# v7-flex2811_single.net
KiCad netlist of a schematic drawn in EAGLE
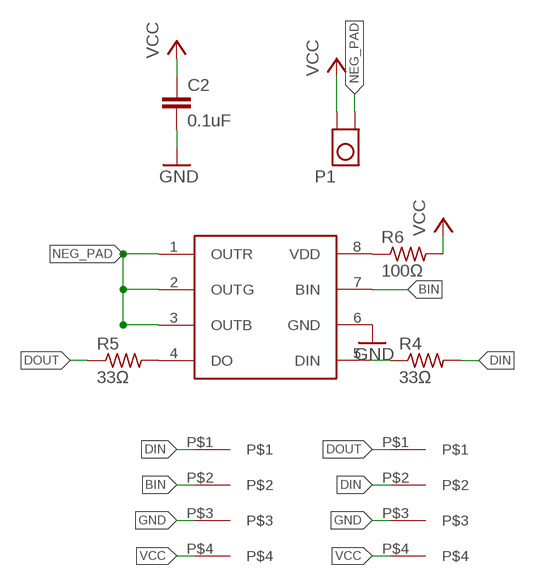
[diagram p0: schematic, sheet 1]

(export (version "E")
  (design (tool "Eeschema 10.0.6"))
  (components
    (comp (ref "C2")
      (value "0.1uF")
      (footprint "eagle-import:C0201")
      (libsource (lib "eagle-import") (part "C-EUC0201"))
    )
    (comp (ref "P1")
      (value "TP_4MM_MED_PAD")
      (footprint "eagle-import:TP_4MM_MED_PAD")
      (libsource (lib "eagle-import") (part "TP_4MM_MED_PAD"))
    )
    (comp (ref "R4")
      (value "33Ω")
      (footprint "eagle-import:R0201")
      (libsource (lib "eagle-import") (part "R-US_R0201"))
    )
    (comp (ref "R5")
      (value "33Ω")
      (footprint "eagle-import:R0201")
      (libsource (lib "eagle-import") (part "R-US_R0201"))
    )
    (comp (ref "R6")
      (value "100Ω")
      (footprint "eagle-import:R0201")
      (libsource (lib "eagle-import") (part "R-US_R0201"))
    )
    (comp (ref "U$3")
      (value "4PAD")
      (footprint "eagle-import:4PAD")
      (libsource (lib "eagle-import") (part "4PAD"))
    )
    (comp (ref "U$4")
      (value "4PAD")
      (footprint "eagle-import:4PAD")
      (libsource (lib "eagle-import") (part "4PAD"))
    )
    (comp (ref "U1")
      (value "WS2818")
      (footprint "eagle-import:SO08")
      (libsource (lib "eagle-import") (part "WS2818"))
    )
  )
  (nets
    (net (code "1") (name "BIN") (class "Default")
      (node (ref "U$3") (pin "P$2") (pinfunction "P$2_P$2") (pintype "bidirectional"))
      (node (ref "U1") (pin "7") (pinfunction "BIN_7") (pintype "bidirectional"))
    )
    (net (code "2") (name "DIN") (class "Default")
      (node (ref "R4") (pin "2") (pinfunction "2_2") (pintype "passive"))
      (node (ref "U$3") (pin "P$1") (pinfunction "P$1_P$1") (pintype "bidirectional"))
      (node (ref "U$4") (pin "P$2") (pinfunction "P$2_P$2") (pintype "bidirectional"))
    )
    (net (code "3") (name "DOUT") (class "Default")
      (node (ref "R5") (pin "1") (pinfunction "1_1") (pintype "passive"))
      (node (ref "U$4") (pin "P$1") (pinfunction "P$1_P$1") (pintype "bidirectional"))
    )
    (net (code "4") (name "GND") (class "Default")
      (node (ref "C2") (pin "2") (pinfunction "2_2") (pintype "passive"))
      (node (ref "U$3") (pin "P$3") (pinfunction "P$3_P$3") (pintype "bidirectional"))
      (node (ref "U$4") (pin "P$3") (pinfunction "P$3_P$3") (pintype "bidirectional"))
      (node (ref "U1") (pin "6") (pinfunction "GND_6") (pintype "bidirectional"))
    )
    (net (code "5") (name "NEG_PAD") (class "Default")
      (node (ref "P1") (pin "P$1") (pinfunction "0_P$1") (pintype "bidirectional"))
      (node (ref "U1") (pin "1") (pinfunction "OUTR_1") (pintype "bidirectional"))
      (node (ref "U1") (pin "2") (pinfunction "OUTG_2") (pintype "bidirectional"))
      (node (ref "U1") (pin "3") (pinfunction "OUTB_3") (pintype "bidirectional"))
    )
    (net (code "6") (name "Net-(U1-DIN)") (class "Default")
      (node (ref "R4") (pin "1") (pinfunction "1_1") (pintype "passive"))
      (node (ref "U1") (pin "5") (pinfunction "DIN_5") (pintype "bidirectional"))
    )
    (net (code "7") (name "Net-(U1-DO)") (class "Default")
      (node (ref "R5") (pin "2") (pinfunction "2_2") (pintype "passive"))
      (node (ref "U1") (pin "4") (pinfunction "DO_4") (pintype "bidirectional"))
    )
    (net (code "8") (name "Net-(U1-VDD)") (class "Default")
      (node (ref "R6") (pin "1") (pinfunction "1_1") (pintype "passive"))
      (node (ref "U1") (pin "8") (pinfunction "VDD_8") (pintype "bidirectional"))
    )
    (net (code "9") (name "VCC") (class "Default")
      (node (ref "C2") (pin "1") (pinfunction "1_1") (pintype "passive"))
      (node (ref "P1") (pin "P$2") (pinfunction "1_P$2") (pintype "bidirectional"))
      (node (ref "R6") (pin "2") (pinfunction "2_2") (pintype "passive"))
      (node (ref "U$3") (pin "P$4") (pinfunction "P$4_P$4") (pintype "bidirectional"))
      (node (ref "U$4") (pin "P$4") (pinfunction "P$4_P$4") (pintype "bidirectional"))
    )
  )
)
